# game_board_v02.net
KiCad netlist of a schematic drawn in EAGLE
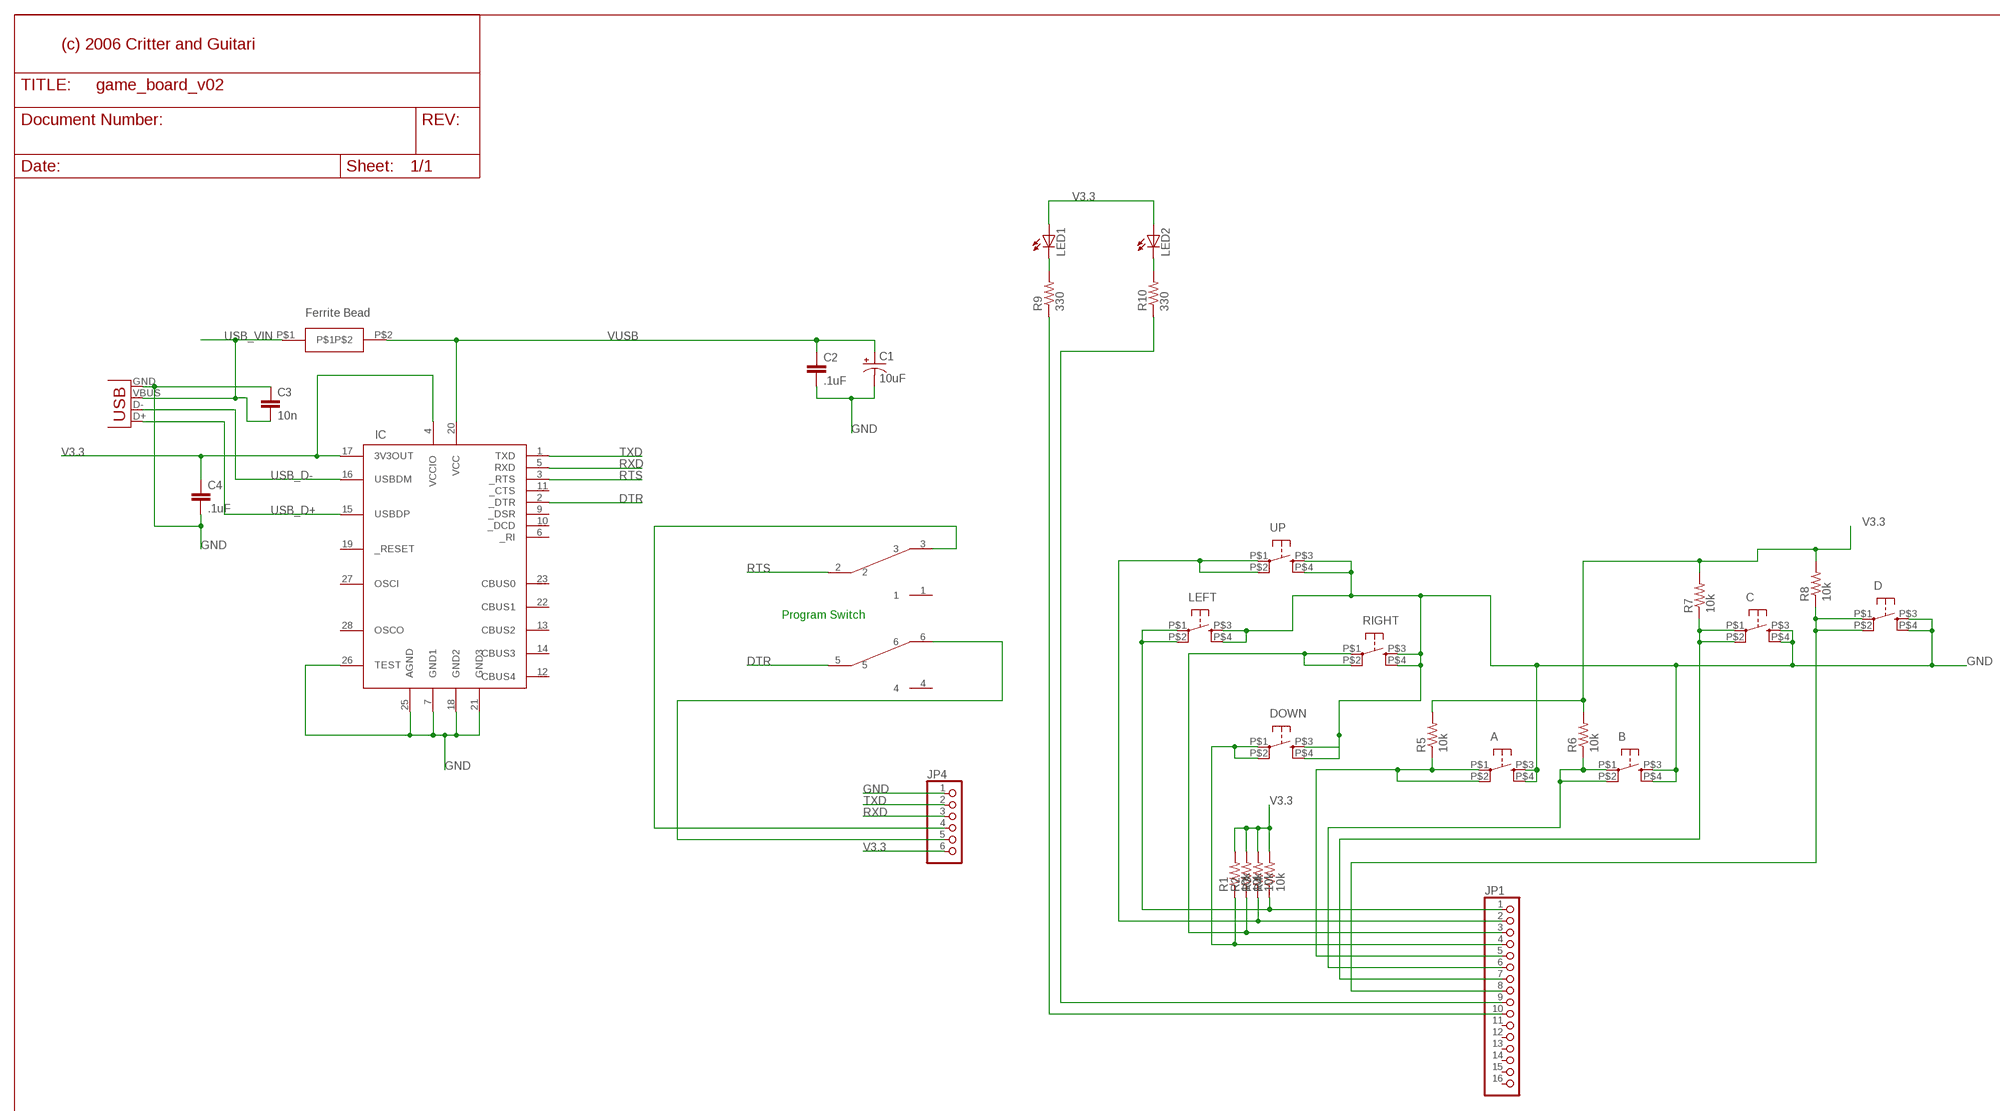
[diagram p0: schematic, sheet 1]

(export (version "E")
  (design (tool "Eeschema 10.0.6"))
  (components
    (comp (ref "A")
      (value "TAC_SWITCHKSA_SEALED_TAC_SWITCH")
      (footprint "eagle-import:KSA_SEALED_TAC_SWITCH")
      (libsource (lib "eagle-import") (part "TAC_SWITCHKSA_SEALED_TAC_SWITCH"))
    )
    (comp (ref "B")
      (value "TAC_SWITCHKSA_SEALED_TAC_SWITCH")
      (footprint "eagle-import:KSA_SEALED_TAC_SWITCH")
      (libsource (lib "eagle-import") (part "TAC_SWITCHKSA_SEALED_TAC_SWITCH"))
    )
    (comp (ref "C")
      (value "TAC_SWITCHKSA_SEALED_TAC_SWITCH")
      (footprint "eagle-import:KSA_SEALED_TAC_SWITCH")
      (libsource (lib "eagle-import") (part "TAC_SWITCHKSA_SEALED_TAC_SWITCH"))
    )
    (comp (ref "C1")
      (value "10uF")
      (footprint "eagle-import:CPOL_1206")
      (libsource (lib "eagle-import") (part "CAP_POL1206"))
    )
    (comp (ref "C2")
      (value ".1uF")
      (footprint "eagle-import:C0603")
      (libsource (lib "eagle-import") (part "CAP0603"))
    )
    (comp (ref "C3")
      (value "10n")
      (footprint "eagle-import:C0603")
      (libsource (lib "eagle-import") (part "CAP0603"))
    )
    (comp (ref "C4")
      (value ".1uF")
      (footprint "eagle-import:C0603")
      (libsource (lib "eagle-import") (part "CAP0603"))
    )
    (comp (ref "D")
      (value "TAC_SWITCHKSA_SEALED_TAC_SWITCH")
      (footprint "eagle-import:KSA_SEALED_TAC_SWITCH")
      (libsource (lib "eagle-import") (part "TAC_SWITCHKSA_SEALED_TAC_SWITCH"))
    )
    (comp (ref "DOWN")
      (value "TAC_SWITCHKSA_SEALED_TAC_SWITCH")
      (footprint "eagle-import:KSA_SEALED_TAC_SWITCH")
      (libsource (lib "eagle-import") (part "TAC_SWITCHKSA_SEALED_TAC_SWITCH"))
    )
    (comp (ref "IC")
      (value "FT232RL")
      (footprint "eagle-import:SSOP28DB")
      (libsource (lib "eagle-import") (part "FT232RL"))
    )
    (comp (ref "JP1")
      (value "PINHD-1X16")
      (footprint "eagle-import:1X16")
      (libsource (lib "eagle-import") (part "PINHD-1X16"))
    )
    (comp (ref "JP4")
      (value "PINHD-1X6")
      (footprint "eagle-import:1X06")
      (libsource (lib "eagle-import") (part "PINHD-1X6"))
    )
    (comp (ref "LED1")
      (value "LED1206")
      (footprint "eagle-import:CHIPLED_1206")
      (libsource (lib "eagle-import") (part "LED1206"))
    )
    (comp (ref "LED2")
      (value "LED1206")
      (footprint "eagle-import:CHIPLED_1206")
      (libsource (lib "eagle-import") (part "LED1206"))
    )
    (comp (ref "LEFT")
      (value "TAC_SWITCHKSA_SEALED_TAC_SWITCH")
      (footprint "eagle-import:KSA_SEALED_TAC_SWITCH")
      (libsource (lib "eagle-import") (part "TAC_SWITCHKSA_SEALED_TAC_SWITCH"))
    )
    (comp (ref "R1")
      (value "10k")
      (footprint "eagle-import:R0603")
      (libsource (lib "eagle-import") (part "RES0603"))
    )
    (comp (ref "R2")
      (value "10k")
      (footprint "eagle-import:R0603")
      (libsource (lib "eagle-import") (part "RES0603"))
    )
    (comp (ref "R3")
      (value "10k")
      (footprint "eagle-import:R0603")
      (libsource (lib "eagle-import") (part "RES0603"))
    )
    (comp (ref "R4")
      (value "10k")
      (footprint "eagle-import:R0603")
      (libsource (lib "eagle-import") (part "RES0603"))
    )
    (comp (ref "R5")
      (value "10k")
      (footprint "eagle-import:R0603")
      (libsource (lib "eagle-import") (part "RES0603"))
    )
    (comp (ref "R6")
      (value "10k")
      (footprint "eagle-import:R0603")
      (libsource (lib "eagle-import") (part "RES0603"))
    )
    (comp (ref "R7")
      (value "10k")
      (footprint "eagle-import:R0603")
      (libsource (lib "eagle-import") (part "RES0603"))
    )
    (comp (ref "R8")
      (value "10k")
      (footprint "eagle-import:R0603")
      (libsource (lib "eagle-import") (part "RES0603"))
    )
    (comp (ref "R9")
      (value "330")
      (footprint "eagle-import:R0603")
      (libsource (lib "eagle-import") (part "RES0603"))
    )
    (comp (ref "R10")
      (value "330")
      (footprint "eagle-import:R0603")
      (libsource (lib "eagle-import") (part "RES0603"))
    )
    (comp (ref "RIGHT")
      (value "TAC_SWITCHKSA_SEALED_TAC_SWITCH")
      (footprint "eagle-import:KSA_SEALED_TAC_SWITCH")
      (libsource (lib "eagle-import") (part "TAC_SWITCHKSA_SEALED_TAC_SWITCH"))
    )
    (comp (ref "U$1")
      (value "FERRITE_BEAD")
      (footprint "eagle-import:FERRITE_BEAD")
      (libsource (lib "eagle-import") (part "FERRITE_BEAD"))
    )
    (comp (ref "U$2")
      (value "SWITCH_DPDT")
      (footprint "eagle-import:SWITCH_DPDT_SMT")
      (libsource (lib "eagle-import") (part "SWITCH_DPDT"))
    )
    (comp (ref "UP")
      (value "TAC_SWITCHKSA_SEALED_TAC_SWITCH")
      (footprint "eagle-import:KSA_SEALED_TAC_SWITCH")
      (libsource (lib "eagle-import") (part "TAC_SWITCHKSA_SEALED_TAC_SWITCH"))
    )
    (comp (ref "X2")
      (value "USB-B-H")
      (footprint "eagle-import:USB-B-H")
      (libsource (lib "eagle-import") (part "USB-B-H"))
    )
  )
  (nets
    (net (code "1") (name "/DTR") (class "Default")
      (node (ref "IC") (pin "2") (pinfunction "_DTR_2") (pintype "output"))
      (node (ref "U$2") (pin "5") (pinfunction "5_5") (pintype "bidirectional"))
    )
    (net (code "2") (name "/GND") (class "Default")
      (node (ref "A") (pin "P$3") (pinfunction "S_P$3") (pintype "passive"))
      (node (ref "A") (pin "P$4") (pinfunction "S1_P$4") (pintype "passive"))
      (node (ref "B") (pin "P$3") (pinfunction "S_P$3") (pintype "passive"))
      (node (ref "B") (pin "P$4") (pinfunction "S1_P$4") (pintype "passive"))
      (node (ref "C") (pin "P$3") (pinfunction "S_P$3") (pintype "passive"))
      (node (ref "C") (pin "P$4") (pinfunction "S1_P$4") (pintype "passive"))
      (node (ref "C1") (pin "C") (pinfunction "-_C") (pintype "passive"))
      (node (ref "C2") (pin "2") (pinfunction "2_2") (pintype "passive"))
      (node (ref "C3") (pin "1") (pinfunction "1_1") (pintype "passive"))
      (node (ref "C4") (pin "2") (pinfunction "2_2") (pintype "passive"))
      (node (ref "D") (pin "P$3") (pinfunction "S_P$3") (pintype "passive"))
      (node (ref "D") (pin "P$4") (pinfunction "S1_P$4") (pintype "passive"))
      (node (ref "DOWN") (pin "P$3") (pinfunction "S_P$3") (pintype "passive"))
      (node (ref "DOWN") (pin "P$4") (pinfunction "S1_P$4") (pintype "passive"))
      (node (ref "IC") (pin "18") (pinfunction "GND2_18") (pintype "power_in"))
      (node (ref "IC") (pin "21") (pinfunction "GND3_21") (pintype "power_in"))
      (node (ref "IC") (pin "25") (pinfunction "AGND_25") (pintype "power_in"))
      (node (ref "IC") (pin "26") (pinfunction "TEST_26") (pintype "input"))
      (node (ref "IC") (pin "7") (pinfunction "GND1_7") (pintype "power_in"))
      (node (ref "JP4") (pin "1") (pinfunction "1_1") (pintype "passive"))
      (node (ref "LEFT") (pin "P$3") (pinfunction "S_P$3") (pintype "passive"))
      (node (ref "LEFT") (pin "P$4") (pinfunction "S1_P$4") (pintype "passive"))
      (node (ref "RIGHT") (pin "P$3") (pinfunction "S_P$3") (pintype "passive"))
      (node (ref "RIGHT") (pin "P$4") (pinfunction "S1_P$4") (pintype "passive"))
      (node (ref "UP") (pin "P$3") (pinfunction "S_P$3") (pintype "passive"))
      (node (ref "UP") (pin "P$4") (pinfunction "S1_P$4") (pintype "passive"))
      (node (ref "X2") (pin "GND") (pinfunction "GND_GND") (pintype "bidirectional"))
    )
    (net (code "3") (name "/RTS") (class "Default")
      (node (ref "IC") (pin "3") (pinfunction "_RTS_3") (pintype "output"))
      (node (ref "U$2") (pin "2") (pinfunction "2_2") (pintype "bidirectional"))
    )
    (net (code "4") (name "/RXD") (class "Default")
      (node (ref "IC") (pin "5") (pinfunction "RXD_5") (pintype "input"))
      (node (ref "JP4") (pin "3") (pinfunction "3_3") (pintype "passive"))
    )
    (net (code "5") (name "/TXD") (class "Default")
      (node (ref "IC") (pin "1") (pinfunction "TXD_1") (pintype "output"))
      (node (ref "JP4") (pin "2") (pinfunction "2_2") (pintype "passive"))
    )
    (net (code "6") (name "/USB_D+") (class "Default")
      (node (ref "IC") (pin "15") (pinfunction "USBDP_15") (pintype "bidirectional"))
      (node (ref "X2") (pin "D+") (pinfunction "D+_D+") (pintype "bidirectional"))
    )
    (net (code "7") (name "/USB_D-") (class "Default")
      (node (ref "IC") (pin "16") (pinfunction "USBDM_16") (pintype "bidirectional"))
      (node (ref "X2") (pin "D-") (pinfunction "D-_D-") (pintype "bidirectional"))
    )
    (net (code "8") (name "/USB_VIN") (class "Default")
      (node (ref "C3") (pin "2") (pinfunction "2_2") (pintype "passive"))
      (node (ref "U$1") (pin "P$1") (pinfunction "P$1_P$1") (pintype "bidirectional"))
      (node (ref "X2") (pin "VBUS") (pinfunction "VBUS_VBUS") (pintype "bidirectional"))
    )
    (net (code "9") (name "/V3.3") (class "Default")
      (node (ref "C4") (pin "1") (pinfunction "1_1") (pintype "passive"))
      (node (ref "IC") (pin "17") (pinfunction "3V3OUT_17") (pintype "output"))
      (node (ref "IC") (pin "4") (pinfunction "VCCIO_4") (pintype "power_in"))
      (node (ref "JP4") (pin "6") (pinfunction "6_6") (pintype "passive"))
      (node (ref "LED1") (pin "A") (pinfunction "A_A") (pintype "passive"))
      (node (ref "LED2") (pin "A") (pinfunction "A_A") (pintype "passive"))
      (node (ref "R1") (pin "2") (pinfunction "2_2") (pintype "passive"))
      (node (ref "R2") (pin "2") (pinfunction "2_2") (pintype "passive"))
      (node (ref "R3") (pin "2") (pinfunction "2_2") (pintype "passive"))
      (node (ref "R4") (pin "2") (pinfunction "2_2") (pintype "passive"))
      (node (ref "R5") (pin "2") (pinfunction "2_2") (pintype "passive"))
      (node (ref "R6") (pin "2") (pinfunction "2_2") (pintype "passive"))
      (node (ref "R7") (pin "2") (pinfunction "2_2") (pintype "passive"))
      (node (ref "R8") (pin "2") (pinfunction "2_2") (pintype "passive"))
    )
    (net (code "10") (name "/VUSB") (class "Default")
      (node (ref "C1") (pin "A") (pinfunction "+_A") (pintype "passive"))
      (node (ref "C2") (pin "1") (pinfunction "1_1") (pintype "passive"))
      (node (ref "IC") (pin "20") (pinfunction "VCC_20") (pintype "power_in"))
      (node (ref "U$1") (pin "P$2") (pinfunction "P$2_P$2") (pintype "bidirectional"))
    )
    (net (code "11") (name "Net-(A-P)") (class "Default")
      (node (ref "A") (pin "P$1") (pinfunction "P_P$1") (pintype "passive"))
      (node (ref "A") (pin "P$2") (pinfunction "P1_P$2") (pintype "passive"))
      (node (ref "JP1") (pin "5") (pinfunction "5_5") (pintype "passive"))
      (node (ref "R5") (pin "1") (pinfunction "1_1") (pintype "passive"))
    )
    (net (code "12") (name "Net-(B-P)") (class "Default")
      (node (ref "B") (pin "P$1") (pinfunction "P_P$1") (pintype "passive"))
      (node (ref "B") (pin "P$2") (pinfunction "P1_P$2") (pintype "passive"))
      (node (ref "JP1") (pin "6") (pinfunction "6_6") (pintype "passive"))
      (node (ref "R6") (pin "1") (pinfunction "1_1") (pintype "passive"))
    )
    (net (code "13") (name "Net-(C-P)") (class "Default")
      (node (ref "C") (pin "P$1") (pinfunction "P_P$1") (pintype "passive"))
      (node (ref "C") (pin "P$2") (pinfunction "P1_P$2") (pintype "passive"))
      (node (ref "JP1") (pin "7") (pinfunction "7_7") (pintype "passive"))
      (node (ref "R7") (pin "1") (pinfunction "1_1") (pintype "passive"))
    )
    (net (code "14") (name "Net-(D-P)") (class "Default")
      (node (ref "D") (pin "P$1") (pinfunction "P_P$1") (pintype "passive"))
      (node (ref "D") (pin "P$2") (pinfunction "P1_P$2") (pintype "passive"))
      (node (ref "JP1") (pin "8") (pinfunction "8_8") (pintype "passive"))
      (node (ref "R8") (pin "1") (pinfunction "1_1") (pintype "passive"))
    )
    (net (code "15") (name "Net-(DOWN-P)") (class "Default")
      (node (ref "DOWN") (pin "P$1") (pinfunction "P_P$1") (pintype "passive"))
      (node (ref "DOWN") (pin "P$2") (pinfunction "P1_P$2") (pintype "passive"))
      (node (ref "JP1") (pin "4") (pinfunction "4_4") (pintype "passive"))
      (node (ref "R1") (pin "1") (pinfunction "1_1") (pintype "passive"))
    )
    (net (code "16") (name "Net-(JP1-Pad9)") (class "Default")
      (node (ref "JP1") (pin "9") (pinfunction "9_9") (pintype "passive"))
      (node (ref "R10") (pin "1") (pinfunction "1_1") (pintype "passive"))
    )
    (net (code "17") (name "Net-(JP1-Pad10)") (class "Default")
      (node (ref "JP1") (pin "10") (pinfunction "10_10") (pintype "passive"))
      (node (ref "R9") (pin "1") (pinfunction "1_1") (pintype "passive"))
    )
    (net (code "18") (name "Net-(JP4-Pad4)") (class "Default")
      (node (ref "JP4") (pin "4") (pinfunction "4_4") (pintype "passive"))
      (node (ref "U$2") (pin "3") (pinfunction "3_3") (pintype "bidirectional"))
    )
    (net (code "19") (name "Net-(JP4-Pad5)") (class "Default")
      (node (ref "JP4") (pin "5") (pinfunction "5_5") (pintype "passive"))
      (node (ref "U$2") (pin "6") (pinfunction "6_6") (pintype "bidirectional"))
    )
    (net (code "20") (name "Net-(LED1-PadC)") (class "Default")
      (node (ref "LED1") (pin "C") (pinfunction "C_C") (pintype "passive"))
      (node (ref "R9") (pin "2") (pinfunction "2_2") (pintype "passive"))
    )
    (net (code "21") (name "Net-(LED2-PadC)") (class "Default")
      (node (ref "LED2") (pin "C") (pinfunction "C_C") (pintype "passive"))
      (node (ref "R10") (pin "2") (pinfunction "2_2") (pintype "passive"))
    )
    (net (code "22") (name "Net-(LEFT-P)") (class "Default")
      (node (ref "JP1") (pin "1") (pinfunction "1_1") (pintype "passive"))
      (node (ref "LEFT") (pin "P$1") (pinfunction "P_P$1") (pintype "passive"))
      (node (ref "LEFT") (pin "P$2") (pinfunction "P1_P$2") (pintype "passive"))
      (node (ref "R4") (pin "1") (pinfunction "1_1") (pintype "passive"))
    )
    (net (code "23") (name "Net-(RIGHT-P)") (class "Default")
      (node (ref "JP1") (pin "3") (pinfunction "3_3") (pintype "passive"))
      (node (ref "R2") (pin "1") (pinfunction "1_1") (pintype "passive"))
      (node (ref "RIGHT") (pin "P$1") (pinfunction "P_P$1") (pintype "passive"))
      (node (ref "RIGHT") (pin "P$2") (pinfunction "P1_P$2") (pintype "passive"))
    )
    (net (code "24") (name "Net-(UP-P)") (class "Default")
      (node (ref "JP1") (pin "2") (pinfunction "2_2") (pintype "passive"))
      (node (ref "R3") (pin "1") (pinfunction "1_1") (pintype "passive"))
      (node (ref "UP") (pin "P$1") (pinfunction "P_P$1") (pintype "passive"))
      (node (ref "UP") (pin "P$2") (pinfunction "P1_P$2") (pintype "passive"))
    )
    (net (code "25") (name "unconnected-(IC-CBUS0-Pad23)") (class "Default")
      (node (ref "IC") (pin "23") (pinfunction "CBUS0_23") (pintype "bidirectional"))
    )
    (net (code "26") (name "unconnected-(IC-CBUS1-Pad22)") (class "Default")
      (node (ref "IC") (pin "22") (pinfunction "CBUS1_22") (pintype "bidirectional"))
    )
    (net (code "27") (name "unconnected-(IC-CBUS2-Pad13)") (class "Default")
      (node (ref "IC") (pin "13") (pinfunction "CBUS2_13") (pintype "bidirectional"))
    )
    (net (code "28") (name "unconnected-(IC-CBUS3-Pad14)") (class "Default")
      (node (ref "IC") (pin "14") (pinfunction "CBUS3_14") (pintype "bidirectional"))
    )
    (net (code "29") (name "unconnected-(IC-CBUS4-Pad12)") (class "Default")
      (node (ref "IC") (pin "12") (pinfunction "CBUS4_12") (pintype "bidirectional"))
    )
    (net (code "30") (name "unconnected-(IC-OSCI-Pad27)") (class "Default")
      (node (ref "IC") (pin "27") (pinfunction "OSCI_27") (pintype "input"))
    )
    (net (code "31") (name "unconnected-(IC-OSCO-Pad28)") (class "Default")
      (node (ref "IC") (pin "28") (pinfunction "OSCO_28") (pintype "output"))
    )
    (net (code "32") (name "unconnected-(IC-_CTS-Pad11)") (class "Default")
      (node (ref "IC") (pin "11") (pinfunction "_CTS_11") (pintype "input"))
    )
    (net (code "33") (name "unconnected-(IC-_DCD-Pad10)") (class "Default")
      (node (ref "IC") (pin "10") (pinfunction "_DCD_10") (pintype "input"))
    )
    (net (code "34") (name "unconnected-(IC-_DSR-Pad9)") (class "Default")
      (node (ref "IC") (pin "9") (pinfunction "_DSR_9") (pintype "input"))
    )
    (net (code "35") (name "unconnected-(IC-_RESET-Pad19)") (class "Default")
      (node (ref "IC") (pin "19") (pinfunction "_RESET_19") (pintype "input"))
    )
    (net (code "36") (name "unconnected-(IC-_RI-Pad6)") (class "Default")
      (node (ref "IC") (pin "6") (pinfunction "_RI_6") (pintype "input"))
    )
    (net (code "37") (name "unconnected-(JP1-Pad11)") (class "Default")
      (node (ref "JP1") (pin "11") (pinfunction "11_11") (pintype "passive"))
    )
    (net (code "38") (name "unconnected-(JP1-Pad12)") (class "Default")
      (node (ref "JP1") (pin "12") (pinfunction "12_12") (pintype "passive"))
    )
    (net (code "39") (name "unconnected-(JP1-Pad13)") (class "Default")
      (node (ref "JP1") (pin "13") (pinfunction "13_13") (pintype "passive"))
    )
    (net (code "40") (name "unconnected-(JP1-Pad14)") (class "Default")
      (node (ref "JP1") (pin "14") (pinfunction "14_14") (pintype "passive"))
    )
    (net (code "41") (name "unconnected-(JP1-Pad15)") (class "Default")
      (node (ref "JP1") (pin "15") (pinfunction "15_15") (pintype "passive"))
    )
    (net (code "42") (name "unconnected-(JP1-Pad16)") (class "Default")
      (node (ref "JP1") (pin "16") (pinfunction "16_16") (pintype "passive"))
    )
    (net (code "43") (name "unconnected-(U$2-Pad1)") (class "Default")
      (node (ref "U$2") (pin "1") (pinfunction "1_1") (pintype "bidirectional"))
    )
    (net (code "44") (name "unconnected-(U$2-Pad4)") (class "Default")
      (node (ref "U$2") (pin "4") (pinfunction "4_4") (pintype "bidirectional"))
    )
  )
)
